# POWER_B1.net
KiCad netlist of a schematic drawn in Altium Designer
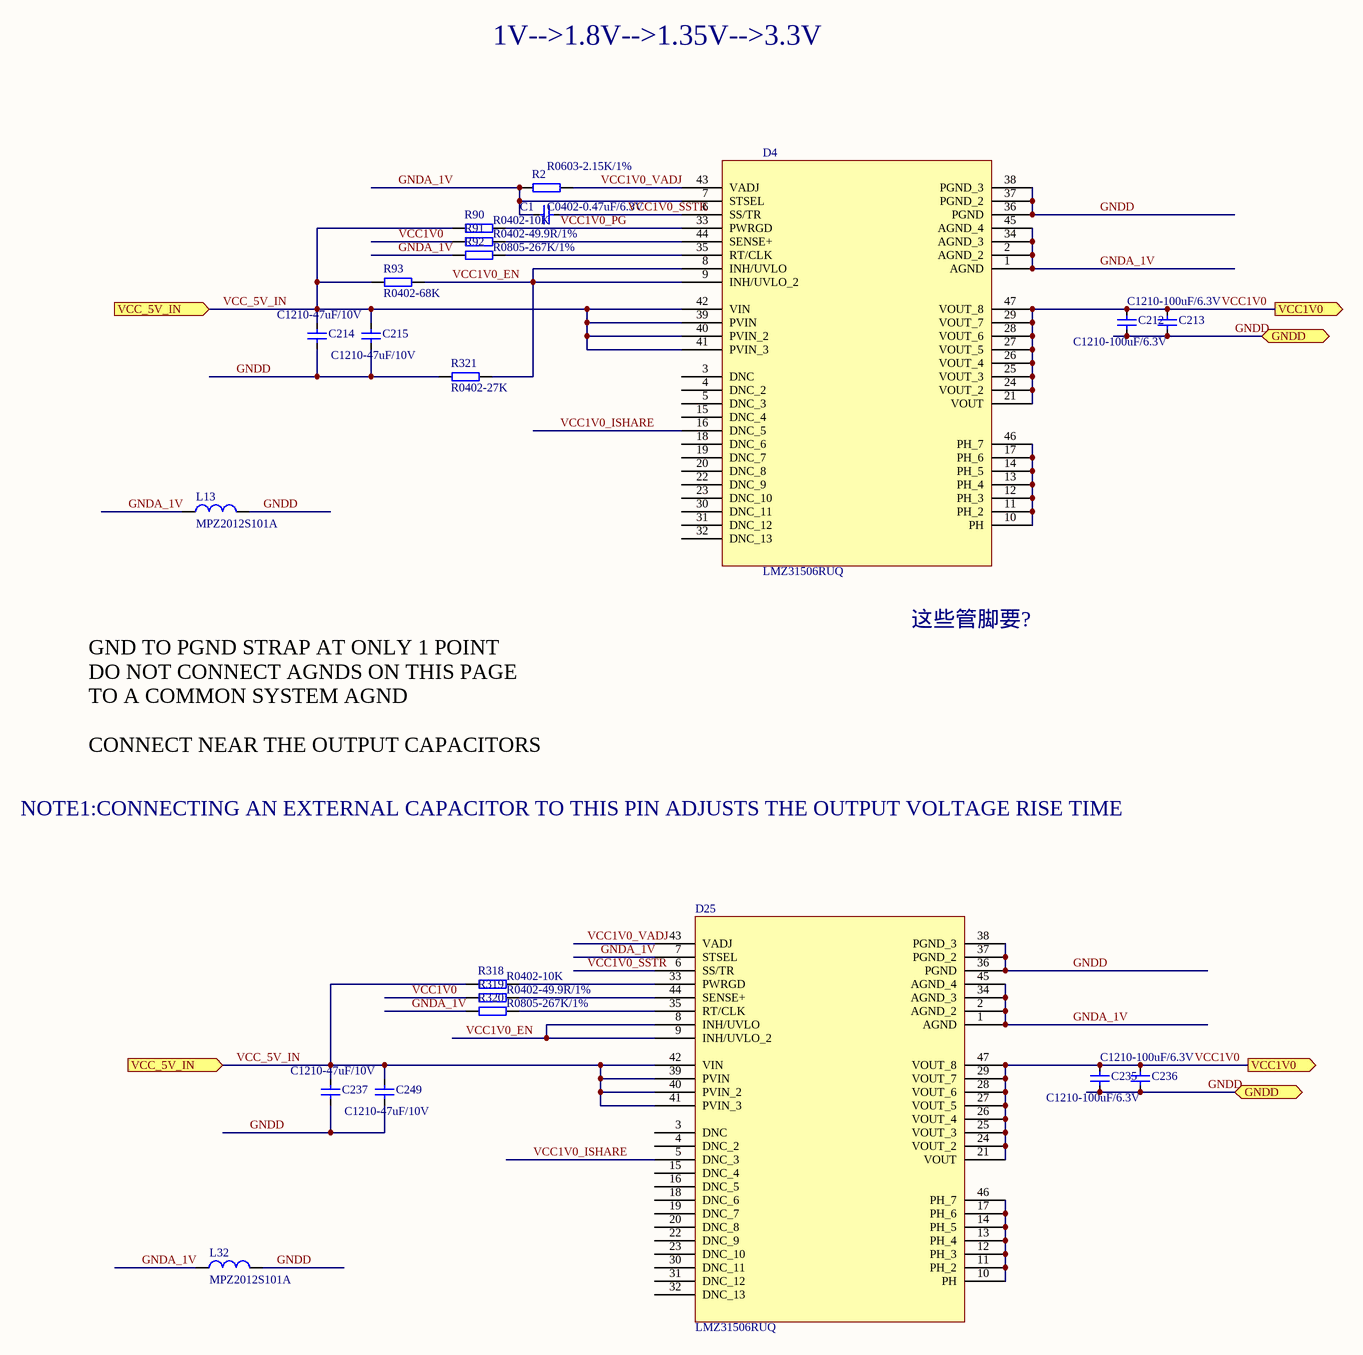
[diagram p0: POWER_B1.SchDoc]

(export (version "E")
  (design (tool "Eeschema 10.0.6"))
  (components
    (comp (ref "C1")
      (value "C0402-0.47uF/6.3V")
      (footprint "C0402")
      (description "X7R")
      (fields (field (name "SCHEMATIC_PART") "CAP") (field (name "MANUFACTURER") "SAMSUNG"))
      (libsource (lib "Database_Libs1") (part "CAP"))
    )
    (comp (ref "C212")
      (value "C1210-100uF/6.3V")
      (footprint "C1210")
      (fields (field (name "SCHEMATIC_PART") "CAP"))
      (libsource (lib "Database_Libs1") (part "CAP"))
    )
    (comp (ref "C213")
      (value "C1210-100uF/6.3V")
      (footprint "C1210")
      (fields (field (name "SCHEMATIC_PART") "CAP"))
      (libsource (lib "Database_Libs1") (part "CAP"))
    )
    (comp (ref "C214")
      (value "C1210-47uF/10V")
      (footprint "C1210")
      (fields (field (name "SCHEMATIC_PART") "CAP"))
      (libsource (lib "Database_Libs1") (part "CAP"))
    )
    (comp (ref "C215")
      (value "C1210-47uF/10V")
      (footprint "C1210")
      (fields (field (name "SCHEMATIC_PART") "CAP"))
      (libsource (lib "Database_Libs1") (part "CAP"))
    )
    (comp (ref "C235")
      (value "C1210-100uF/6.3V")
      (footprint "C1210")
      (fields (field (name "SCHEMATIC_PART") "CAP"))
      (libsource (lib "Database_Libs1") (part "CAP"))
    )
    (comp (ref "C236")
      (value "C1210-100uF/6.3V")
      (footprint "C1210")
      (fields (field (name "SCHEMATIC_PART") "CAP"))
      (libsource (lib "Database_Libs1") (part "CAP"))
    )
    (comp (ref "C237")
      (value "C1210-47uF/10V")
      (footprint "C1210")
      (fields (field (name "SCHEMATIC_PART") "CAP"))
      (libsource (lib "Database_Libs1") (part "CAP"))
    )
    (comp (ref "C249")
      (value "C1210-47uF/10V")
      (footprint "C1210")
      (fields (field (name "SCHEMATIC_PART") "CAP"))
      (libsource (lib "Database_Libs1") (part "CAP"))
    )
    (comp (ref "D4")
      (value "LMZ31506RUQ")
      (footprint "RUQ_47")
      (libsource (lib "SCHLIB1") (part "LMZ31506H_RUQ_47"))
    )
    (comp (ref "D25")
      (value "LMZ31506RUQ")
      (footprint "RUQ_47")
      (libsource (lib "SCHLIB1") (part "LMZ31506H_RUQ_47"))
    )
    (comp (ref "L13")
      (value "MPZ2012S101A")
      (footprint "R0805")
      (fields (field (name "SCHEMATIC_PART") "BEAD") (field (name "MANUFACTURER") "TDK"))
      (libsource (lib "Database_Libs1") (part "BEAD"))
    )
    (comp (ref "L32")
      (value "MPZ2012S101A")
      (footprint "R0805")
      (fields (field (name "SCHEMATIC_PART") "BEAD") (field (name "MANUFACTURER") "TDK"))
      (libsource (lib "Database_Libs1") (part "BEAD"))
    )
    (comp (ref "R2")
      (value "R0603-2.15K/1%")
      (footprint "R0603")
      (fields (field (name "SCHEMATIC_PART") "RES") (field (name "MANUFACTURER") "HKT"))
      (libsource (lib "Database_Libs1") (part "RES"))
    )
    (comp (ref "R90")
      (value "R0402-10K")
      (footprint "R0402")
      (fields (field (name "SCHEMATIC_PART") "RES") (field (name "MANUFACTURER") "SAMSUNG"))
      (libsource (lib "Database_Libs1") (part "RES"))
    )
    (comp (ref "R91")
      (value "R0402-49.9R/1%")
      (footprint "R0402")
      (fields (field (name "SCHEMATIC_PART") "RES") (field (name "MANUFACTURER") "SUPEROHM"))
      (libsource (lib "Database_Libs1") (part "RES"))
    )
    (comp (ref "R92")
      (value "R0805-267K/1%")
      (footprint "R0805")
      (fields (field (name "SCHEMATIC_PART") "RES") (field (name "MANUFACTURER") "SAMSUNG"))
      (libsource (lib "Database_Libs1") (part "RES"))
    )
    (comp (ref "R93")
      (value "R0402-68K")
      (footprint "R0402")
      (fields (field (name "SCHEMATIC_PART") "RES") (field (name "MANUFACTURER") "SAMSUNG"))
      (libsource (lib "Database_Libs1") (part "RES"))
    )
    (comp (ref "R318")
      (value "R0402-10K")
      (footprint "R0402")
      (fields (field (name "SCHEMATIC_PART") "RES") (field (name "MANUFACTURER") "SAMSUNG"))
      (libsource (lib "Database_Libs1") (part "RES"))
    )
    (comp (ref "R319")
      (value "R0402-49.9R/1%")
      (footprint "R0402")
      (fields (field (name "SCHEMATIC_PART") "RES") (field (name "MANUFACTURER") "SUPEROHM"))
      (libsource (lib "Database_Libs1") (part "RES"))
    )
    (comp (ref "R320")
      (value "R0805-267K/1%")
      (footprint "R0805")
      (fields (field (name "SCHEMATIC_PART") "RES") (field (name "MANUFACTURER") "SAMSUNG"))
      (libsource (lib "Database_Libs1") (part "RES"))
    )
    (comp (ref "R321")
      (value "R0402-27K")
      (footprint "R0402")
      (fields (field (name "SCHEMATIC_PART") "RES") (field (name "MANUFACTURER") "SAMSUNG"))
      (libsource (lib "Database_Libs1") (part "RES"))
    )
  )
  (nets
    (net (code "1") (name "/GNDA_1V") (class "Default")
      (node (ref "C1") (pin "1") (pinfunction "1_1") (pintype "passive"))
      (node (ref "D25") (pin "1") (pinfunction "AGND_1") (pintype "passive"))
      (node (ref "D25") (pin "2") (pinfunction "AGND_2_2") (pintype "passive"))
      (node (ref "D25") (pin "34") (pinfunction "AGND_3_34") (pintype "passive"))
      (node (ref "D25") (pin "45") (pinfunction "AGND_4_45") (pintype "passive"))
      (node (ref "D25") (pin "7") (pinfunction "STSEL_7") (pintype "passive"))
      (node (ref "D4") (pin "1") (pinfunction "AGND_1") (pintype "passive"))
      (node (ref "D4") (pin "2") (pinfunction "AGND_2_2") (pintype "passive"))
      (node (ref "D4") (pin "34") (pinfunction "AGND_3_34") (pintype "passive"))
      (node (ref "D4") (pin "45") (pinfunction "AGND_4_45") (pintype "passive"))
      (node (ref "D4") (pin "7") (pinfunction "STSEL_7") (pintype "passive"))
      (node (ref "L13") (pin "1") (pinfunction "1_1") (pintype "passive"))
      (node (ref "L32") (pin "1") (pinfunction "1_1") (pintype "passive"))
      (node (ref "R2") (pin "1") (pintype "passive"))
      (node (ref "R320") (pin "1") (pintype "passive"))
      (node (ref "R92") (pin "1") (pintype "passive"))
    )
    (net (code "2") (name "/GNDD") (class "Default")
      (node (ref "C212") (pin "2") (pinfunction "2_2") (pintype "passive"))
      (node (ref "C213") (pin "2") (pinfunction "2_2") (pintype "passive"))
      (node (ref "C214") (pin "2") (pinfunction "2_2") (pintype "passive"))
      (node (ref "C215") (pin "2") (pinfunction "2_2") (pintype "passive"))
      (node (ref "C235") (pin "2") (pinfunction "2_2") (pintype "passive"))
      (node (ref "C236") (pin "2") (pinfunction "2_2") (pintype "passive"))
      (node (ref "C237") (pin "2") (pinfunction "2_2") (pintype "passive"))
      (node (ref "C249") (pin "2") (pinfunction "2_2") (pintype "passive"))
      (node (ref "D25") (pin "36") (pinfunction "PGND_36") (pintype "passive"))
      (node (ref "D25") (pin "37") (pinfunction "PGND_2_37") (pintype "passive"))
      (node (ref "D25") (pin "38") (pinfunction "PGND_3_38") (pintype "passive"))
      (node (ref "D4") (pin "36") (pinfunction "PGND_36") (pintype "passive"))
      (node (ref "D4") (pin "37") (pinfunction "PGND_2_37") (pintype "passive"))
      (node (ref "D4") (pin "38") (pinfunction "PGND_3_38") (pintype "passive"))
      (node (ref "L13") (pin "2") (pinfunction "2_2") (pintype "passive"))
      (node (ref "L32") (pin "2") (pinfunction "2_2") (pintype "passive"))
      (node (ref "R321") (pin "1") (pintype "passive"))
    )
    (net (code "3") (name "/VCC1V0") (class "Default")
      (node (ref "C212") (pin "1") (pinfunction "1_1") (pintype "passive"))
      (node (ref "C213") (pin "1") (pinfunction "1_1") (pintype "passive"))
      (node (ref "C235") (pin "1") (pinfunction "1_1") (pintype "passive"))
      (node (ref "C236") (pin "1") (pinfunction "1_1") (pintype "passive"))
      (node (ref "D25") (pin "21") (pinfunction "VOUT_21") (pintype "passive"))
      (node (ref "D25") (pin "24") (pinfunction "VOUT_2_24") (pintype "passive"))
      (node (ref "D25") (pin "25") (pinfunction "VOUT_3_25") (pintype "passive"))
      (node (ref "D25") (pin "26") (pinfunction "VOUT_4_26") (pintype "passive"))
      (node (ref "D25") (pin "27") (pinfunction "VOUT_5_27") (pintype "passive"))
      (node (ref "D25") (pin "28") (pinfunction "VOUT_6_28") (pintype "passive"))
      (node (ref "D25") (pin "29") (pinfunction "VOUT_7_29") (pintype "passive"))
      (node (ref "D25") (pin "47") (pinfunction "VOUT_8_47") (pintype "passive"))
      (node (ref "D4") (pin "21") (pinfunction "VOUT_21") (pintype "passive"))
      (node (ref "D4") (pin "24") (pinfunction "VOUT_2_24") (pintype "passive"))
      (node (ref "D4") (pin "25") (pinfunction "VOUT_3_25") (pintype "passive"))
      (node (ref "D4") (pin "26") (pinfunction "VOUT_4_26") (pintype "passive"))
      (node (ref "D4") (pin "27") (pinfunction "VOUT_5_27") (pintype "passive"))
      (node (ref "D4") (pin "28") (pinfunction "VOUT_6_28") (pintype "passive"))
      (node (ref "D4") (pin "29") (pinfunction "VOUT_7_29") (pintype "passive"))
      (node (ref "D4") (pin "47") (pinfunction "VOUT_8_47") (pintype "passive"))
      (node (ref "R319") (pin "1") (pintype "passive"))
      (node (ref "R91") (pin "1") (pintype "passive"))
    )
    (net (code "4") (name "/VCC1V0_EN") (class "Default")
      (node (ref "D25") (pin "8") (pinfunction "INH/UVLO_8") (pintype "passive"))
      (node (ref "D25") (pin "9") (pinfunction "INH/UVLO_2_9") (pintype "passive"))
      (node (ref "D4") (pin "8") (pinfunction "INH/UVLO_8") (pintype "passive"))
      (node (ref "D4") (pin "9") (pinfunction "INH/UVLO_2_9") (pintype "passive"))
      (node (ref "R321") (pin "2") (pintype "passive"))
      (node (ref "R93") (pin "2") (pintype "passive"))
    )
    (net (code "5") (name "/VCC1V0_ISHARE") (class "Default")
      (node (ref "D25") (pin "5") (pinfunction "DNC_3_5") (pintype "passive"))
      (node (ref "D4") (pin "16") (pinfunction "DNC_5_16") (pintype "passive"))
    )
    (net (code "6") (name "/VCC1V0_PG") (class "Default")
      (node (ref "D4") (pin "33") (pinfunction "PWRGD_33") (pintype "passive"))
      (node (ref "R90") (pin "2") (pintype "passive"))
    )
    (net (code "7") (name "/VCC1V0_SSTR") (class "Default")
      (node (ref "C1") (pin "2") (pinfunction "2_2") (pintype "passive"))
      (node (ref "D25") (pin "6") (pinfunction "SS/TR_6") (pintype "passive"))
      (node (ref "D4") (pin "6") (pinfunction "SS/TR_6") (pintype "passive"))
    )
    (net (code "8") (name "/VCC1V0_VADJ") (class "Default")
      (node (ref "D25") (pin "43") (pinfunction "VADJ_43") (pintype "passive"))
      (node (ref "D4") (pin "43") (pinfunction "VADJ_43") (pintype "passive"))
      (node (ref "R2") (pin "2") (pintype "passive"))
    )
    (net (code "9") (name "/VCC_5V_IN") (class "Default")
      (node (ref "C214") (pin "1") (pinfunction "1_1") (pintype "passive"))
      (node (ref "C215") (pin "1") (pinfunction "1_1") (pintype "passive"))
      (node (ref "C237") (pin "1") (pinfunction "1_1") (pintype "passive"))
      (node (ref "C249") (pin "1") (pinfunction "1_1") (pintype "passive"))
      (node (ref "D25") (pin "39") (pinfunction "PVIN_39") (pintype "passive"))
      (node (ref "D25") (pin "40") (pinfunction "PVIN_2_40") (pintype "passive"))
      (node (ref "D25") (pin "41") (pinfunction "PVIN_3_41") (pintype "passive"))
      (node (ref "D25") (pin "42") (pinfunction "VIN_42") (pintype "passive"))
      (node (ref "D4") (pin "39") (pinfunction "PVIN_39") (pintype "passive"))
      (node (ref "D4") (pin "40") (pinfunction "PVIN_2_40") (pintype "passive"))
      (node (ref "D4") (pin "41") (pinfunction "PVIN_3_41") (pintype "passive"))
      (node (ref "D4") (pin "42") (pinfunction "VIN_42") (pintype "passive"))
      (node (ref "R318") (pin "1") (pintype "passive"))
      (node (ref "R90") (pin "1") (pintype "passive"))
      (node (ref "R93") (pin "1") (pintype "passive"))
    )
    (net (code "10") (name "Net-(D4-PH)") (class "Default")
      (node (ref "D4") (pin "10") (pinfunction "PH_10") (pintype "passive"))
      (node (ref "D4") (pin "11") (pinfunction "PH_2_11") (pintype "passive"))
      (node (ref "D4") (pin "12") (pinfunction "PH_3_12") (pintype "passive"))
      (node (ref "D4") (pin "13") (pinfunction "PH_4_13") (pintype "passive"))
      (node (ref "D4") (pin "14") (pinfunction "PH_5_14") (pintype "passive"))
      (node (ref "D4") (pin "17") (pinfunction "PH_6_17") (pintype "passive"))
      (node (ref "D4") (pin "46") (pinfunction "PH_7_46") (pintype "passive"))
    )
    (net (code "11") (name "Net-(D4-RT{slash}CLK)") (class "Default")
      (node (ref "D4") (pin "35") (pinfunction "RT/CLK_35") (pintype "passive"))
      (node (ref "R92") (pin "2") (pintype "passive"))
    )
    (net (code "12") (name "Net-(D4-SENSE+)") (class "Default")
      (node (ref "D4") (pin "44") (pinfunction "SENSE+_44") (pintype "passive"))
      (node (ref "R91") (pin "2") (pintype "passive"))
    )
    (net (code "13") (name "Net-(D25-PH)") (class "Default")
      (node (ref "D25") (pin "10") (pinfunction "PH_10") (pintype "passive"))
      (node (ref "D25") (pin "11") (pinfunction "PH_2_11") (pintype "passive"))
      (node (ref "D25") (pin "12") (pinfunction "PH_3_12") (pintype "passive"))
      (node (ref "D25") (pin "13") (pinfunction "PH_4_13") (pintype "passive"))
      (node (ref "D25") (pin "14") (pinfunction "PH_5_14") (pintype "passive"))
      (node (ref "D25") (pin "17") (pinfunction "PH_6_17") (pintype "passive"))
      (node (ref "D25") (pin "46") (pinfunction "PH_7_46") (pintype "passive"))
    )
    (net (code "14") (name "Net-(D25-PWRGD)") (class "Default")
      (node (ref "D25") (pin "33") (pinfunction "PWRGD_33") (pintype "passive"))
      (node (ref "R318") (pin "2") (pintype "passive"))
    )
    (net (code "15") (name "Net-(D25-RT{slash}CLK)") (class "Default")
      (node (ref "D25") (pin "35") (pinfunction "RT/CLK_35") (pintype "passive"))
      (node (ref "R320") (pin "2") (pintype "passive"))
    )
    (net (code "16") (name "Net-(D25-SENSE+)") (class "Default")
      (node (ref "D25") (pin "44") (pinfunction "SENSE+_44") (pintype "passive"))
      (node (ref "R319") (pin "2") (pintype "passive"))
    )
    (net (code "17") (name "unconnected-(D4-DNC-Pad3)") (class "Default")
      (node (ref "D4") (pin "3") (pinfunction "DNC_3") (pintype "passive"))
    )
    (net (code "18") (name "unconnected-(D4-DNC_2-Pad4)") (class "Default")
      (node (ref "D4") (pin "4") (pinfunction "DNC_2_4") (pintype "passive"))
    )
    (net (code "19") (name "unconnected-(D4-DNC_3-Pad5)") (class "Default")
      (node (ref "D4") (pin "5") (pinfunction "DNC_3_5") (pintype "passive"))
    )
    (net (code "20") (name "unconnected-(D4-DNC_4-Pad15)") (class "Default")
      (node (ref "D4") (pin "15") (pinfunction "DNC_4_15") (pintype "passive"))
    )
    (net (code "21") (name "unconnected-(D4-DNC_6-Pad18)") (class "Default")
      (node (ref "D4") (pin "18") (pinfunction "DNC_6_18") (pintype "passive"))
    )
    (net (code "22") (name "unconnected-(D4-DNC_7-Pad19)") (class "Default")
      (node (ref "D4") (pin "19") (pinfunction "DNC_7_19") (pintype "passive"))
    )
    (net (code "23") (name "unconnected-(D4-DNC_8-Pad20)") (class "Default")
      (node (ref "D4") (pin "20") (pinfunction "DNC_8_20") (pintype "passive"))
    )
    (net (code "24") (name "unconnected-(D4-DNC_9-Pad22)") (class "Default")
      (node (ref "D4") (pin "22") (pinfunction "DNC_9_22") (pintype "passive"))
    )
    (net (code "25") (name "unconnected-(D4-DNC_10-Pad23)") (class "Default")
      (node (ref "D4") (pin "23") (pinfunction "DNC_10_23") (pintype "passive"))
    )
    (net (code "26") (name "unconnected-(D4-DNC_11-Pad30)") (class "Default")
      (node (ref "D4") (pin "30") (pinfunction "DNC_11_30") (pintype "passive"))
    )
    (net (code "27") (name "unconnected-(D4-DNC_12-Pad31)") (class "Default")
      (node (ref "D4") (pin "31") (pinfunction "DNC_12_31") (pintype "passive"))
    )
    (net (code "28") (name "unconnected-(D4-DNC_13-Pad32)") (class "Default")
      (node (ref "D4") (pin "32") (pinfunction "DNC_13_32") (pintype "passive"))
    )
    (net (code "29") (name "unconnected-(D25-DNC-Pad3)") (class "Default")
      (node (ref "D25") (pin "3") (pinfunction "DNC_3") (pintype "passive"))
    )
    (net (code "30") (name "unconnected-(D25-DNC_2-Pad4)") (class "Default")
      (node (ref "D25") (pin "4") (pinfunction "DNC_2_4") (pintype "passive"))
    )
    (net (code "31") (name "unconnected-(D25-DNC_4-Pad15)") (class "Default")
      (node (ref "D25") (pin "15") (pinfunction "DNC_4_15") (pintype "passive"))
    )
    (net (code "32") (name "unconnected-(D25-DNC_5-Pad16)") (class "Default")
      (node (ref "D25") (pin "16") (pinfunction "DNC_5_16") (pintype "passive"))
    )
    (net (code "33") (name "unconnected-(D25-DNC_6-Pad18)") (class "Default")
      (node (ref "D25") (pin "18") (pinfunction "DNC_6_18") (pintype "passive"))
    )
    (net (code "34") (name "unconnected-(D25-DNC_7-Pad19)") (class "Default")
      (node (ref "D25") (pin "19") (pinfunction "DNC_7_19") (pintype "passive"))
    )
    (net (code "35") (name "unconnected-(D25-DNC_8-Pad20)") (class "Default")
      (node (ref "D25") (pin "20") (pinfunction "DNC_8_20") (pintype "passive"))
    )
    (net (code "36") (name "unconnected-(D25-DNC_9-Pad22)") (class "Default")
      (node (ref "D25") (pin "22") (pinfunction "DNC_9_22") (pintype "passive"))
    )
    (net (code "37") (name "unconnected-(D25-DNC_10-Pad23)") (class "Default")
      (node (ref "D25") (pin "23") (pinfunction "DNC_10_23") (pintype "passive"))
    )
    (net (code "38") (name "unconnected-(D25-DNC_11-Pad30)") (class "Default")
      (node (ref "D25") (pin "30") (pinfunction "DNC_11_30") (pintype "passive"))
    )
    (net (code "39") (name "unconnected-(D25-DNC_12-Pad31)") (class "Default")
      (node (ref "D25") (pin "31") (pinfunction "DNC_12_31") (pintype "passive"))
    )
    (net (code "40") (name "unconnected-(D25-DNC_13-Pad32)") (class "Default")
      (node (ref "D25") (pin "32") (pinfunction "DNC_13_32") (pintype "passive"))
    )
  )
)
